# mbed-WiFi-BLE-Cloud-v1_0_0.net
KiCad netlist of a schematic drawn in EAGLE
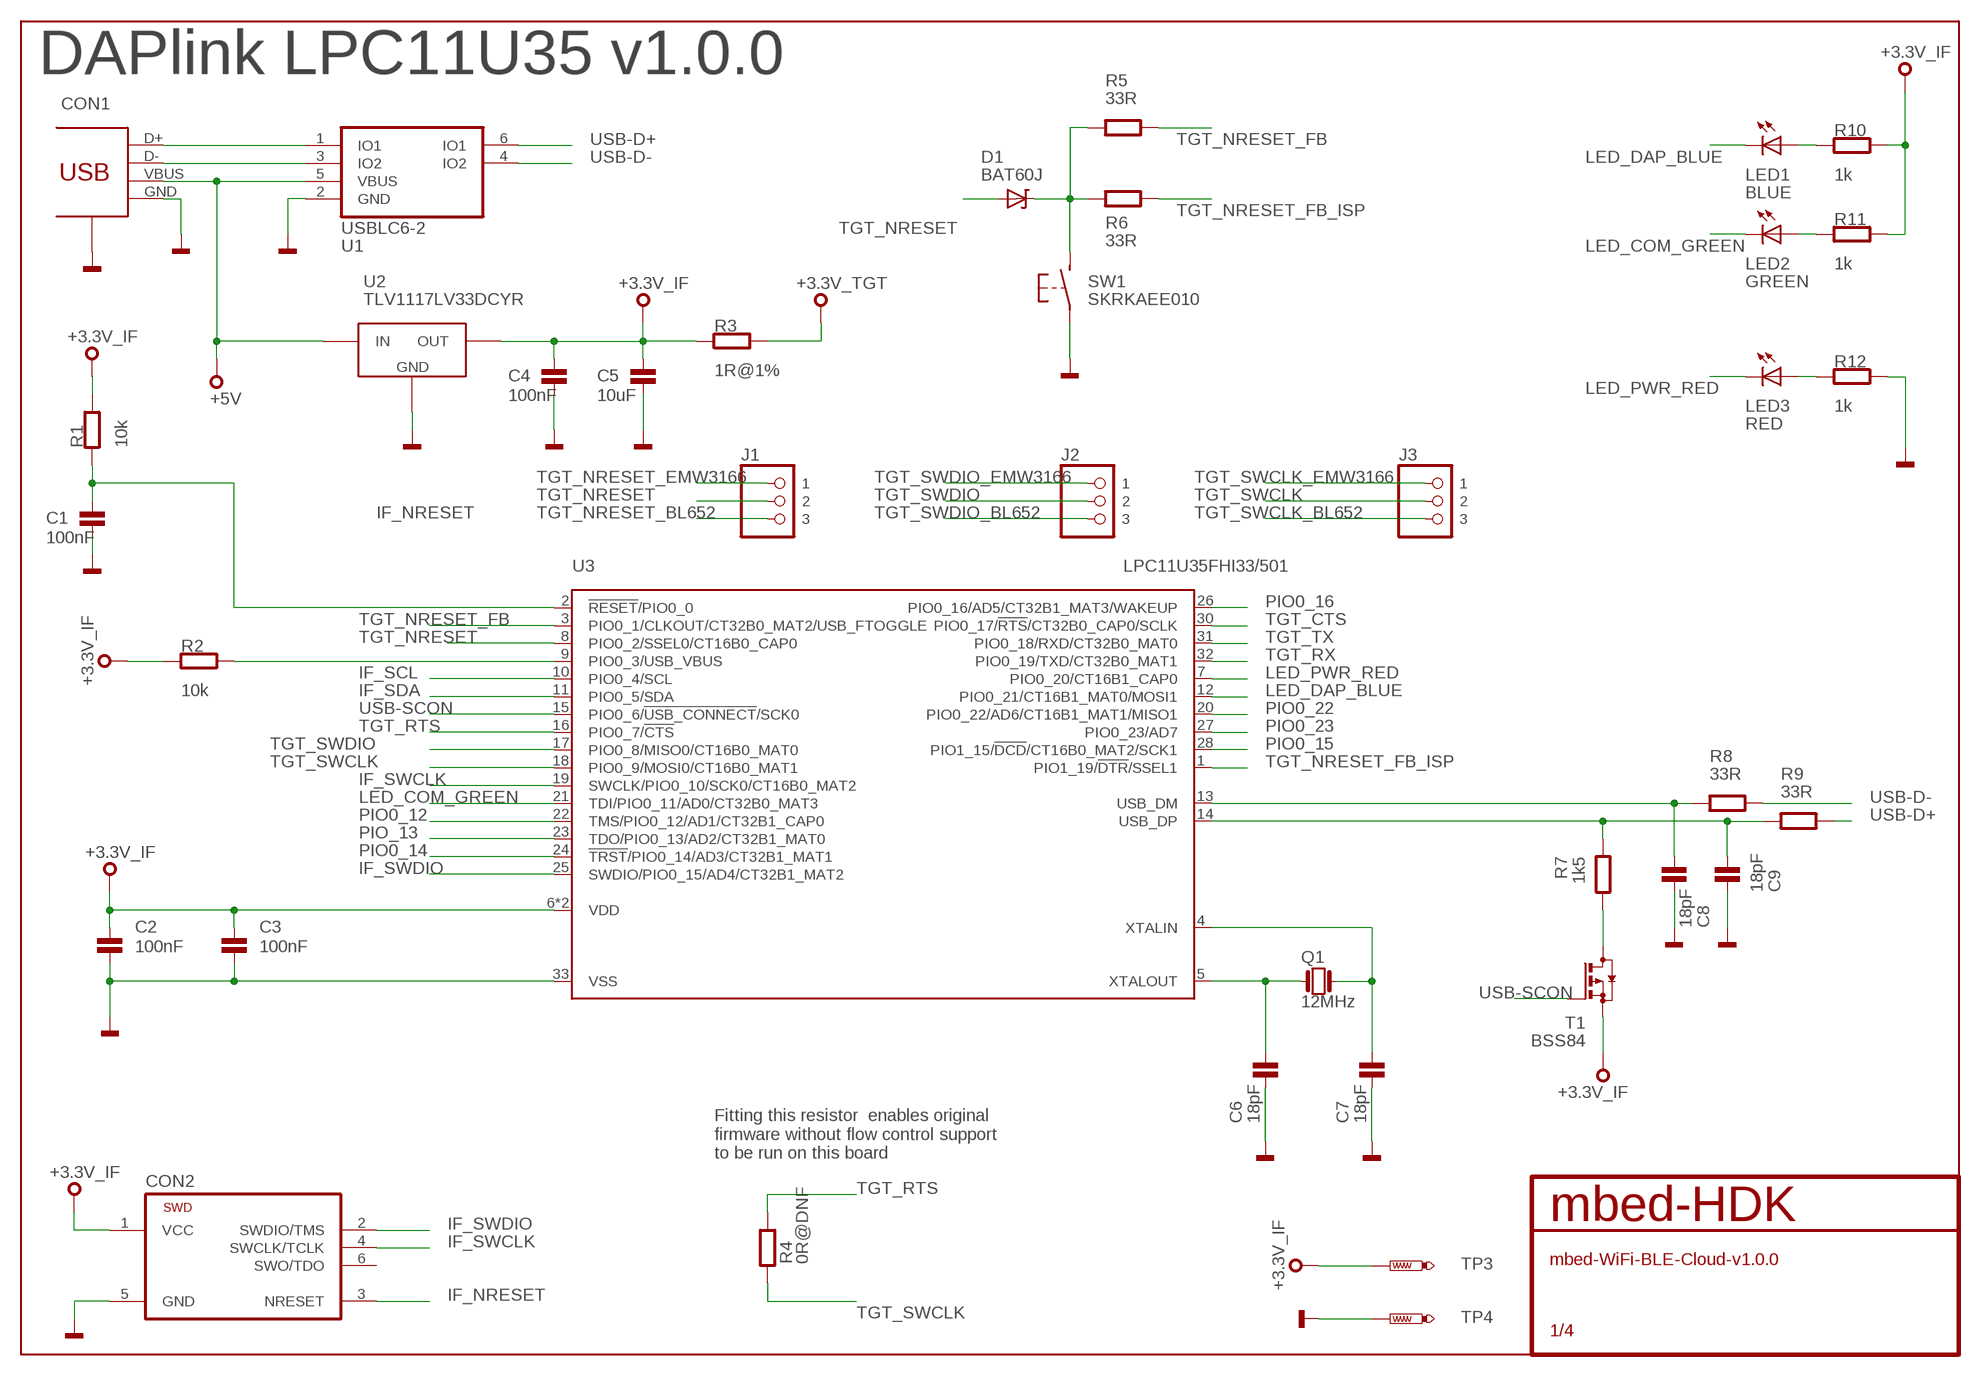
[diagram p0: schematic, sheet 1]
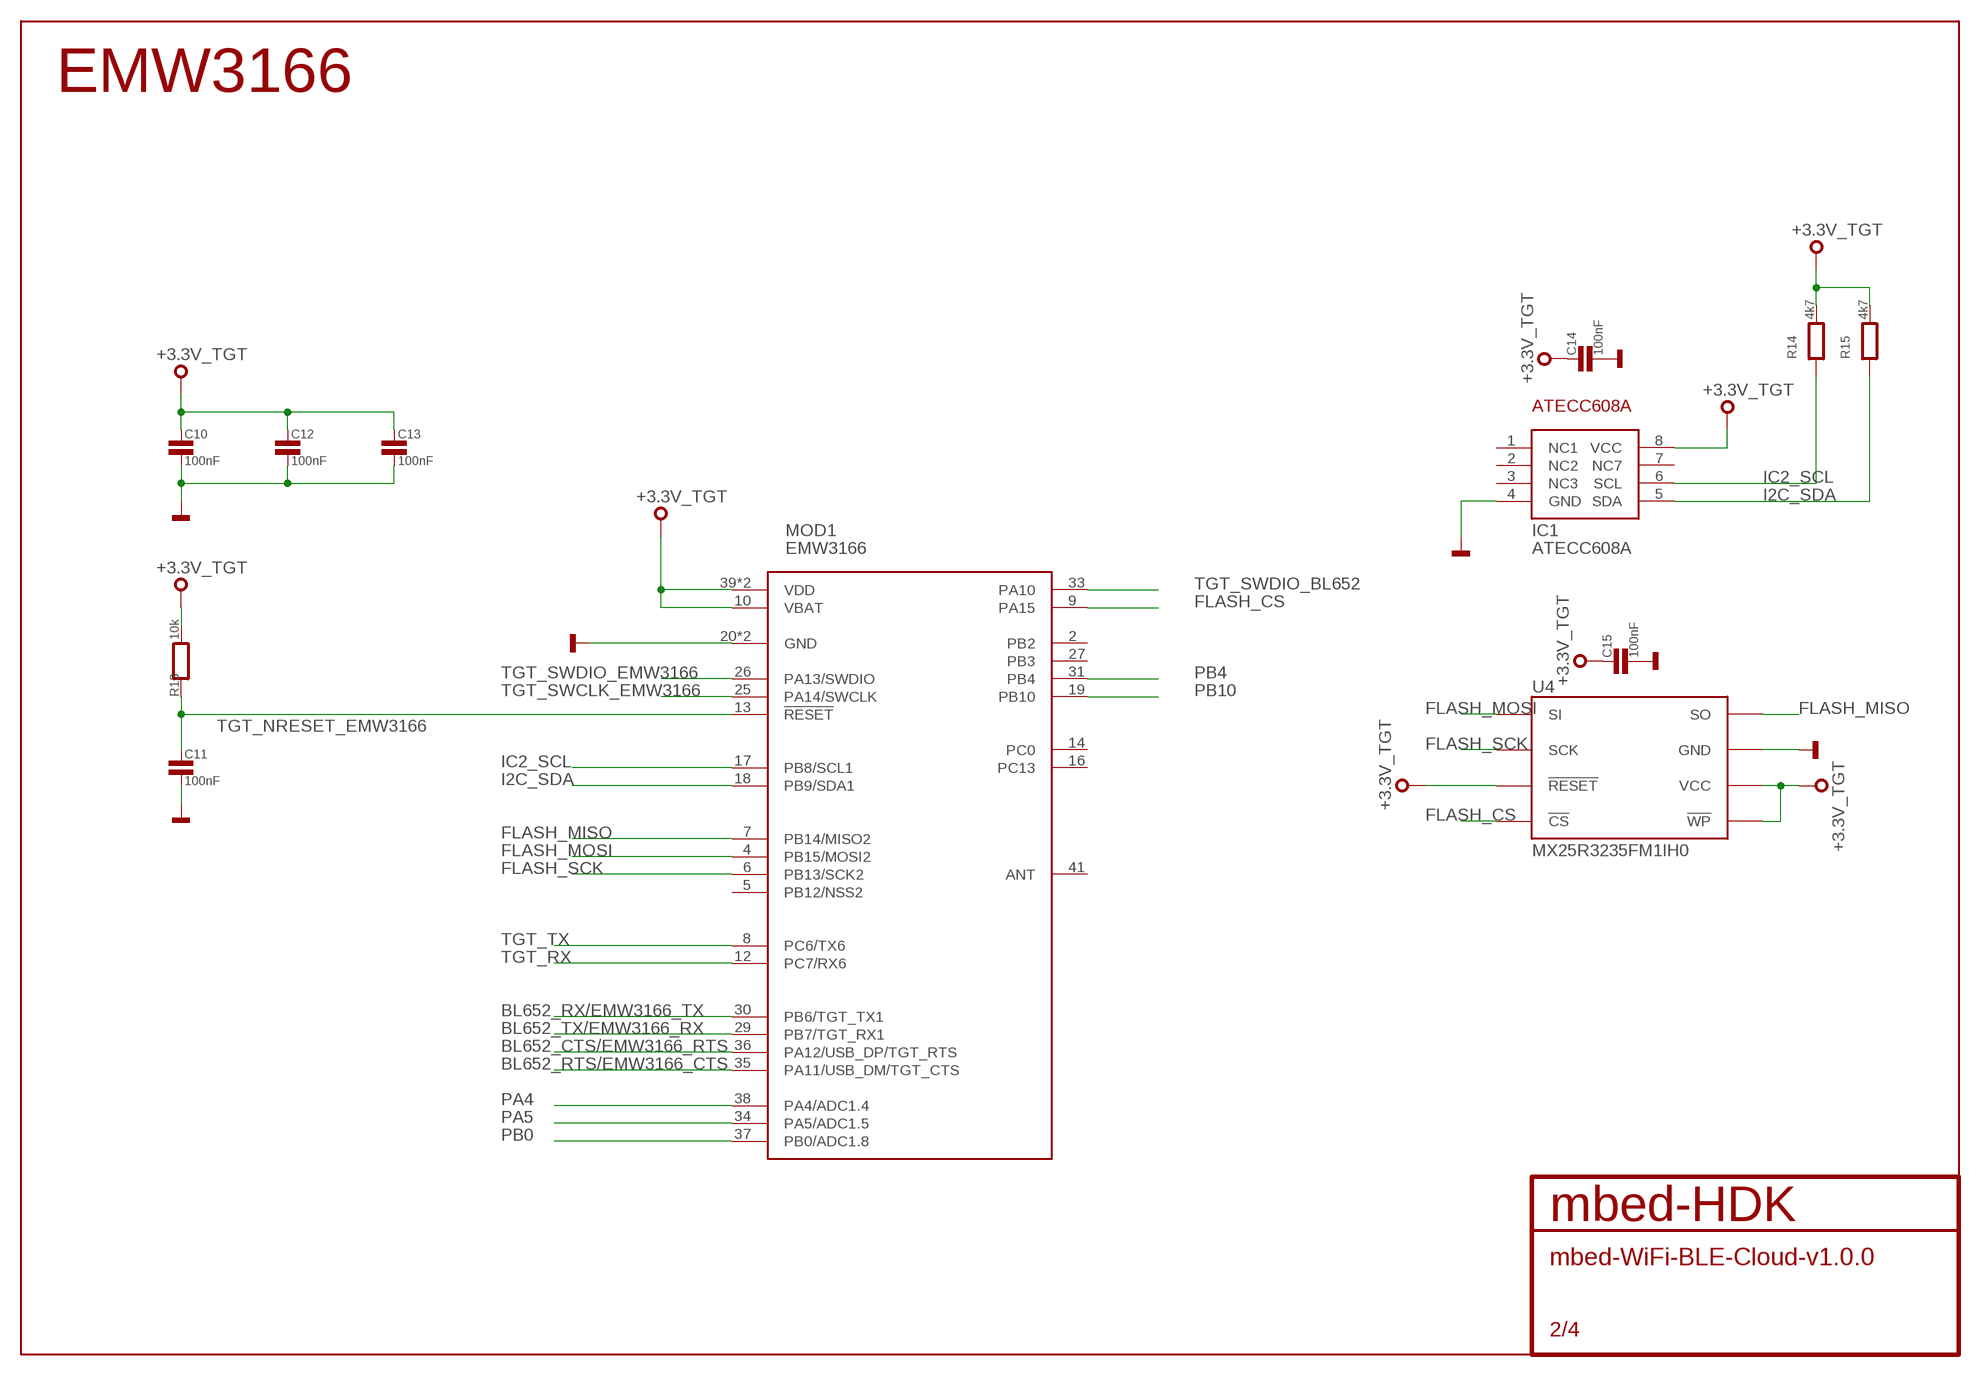
[diagram p1: schematic, sheet 2]
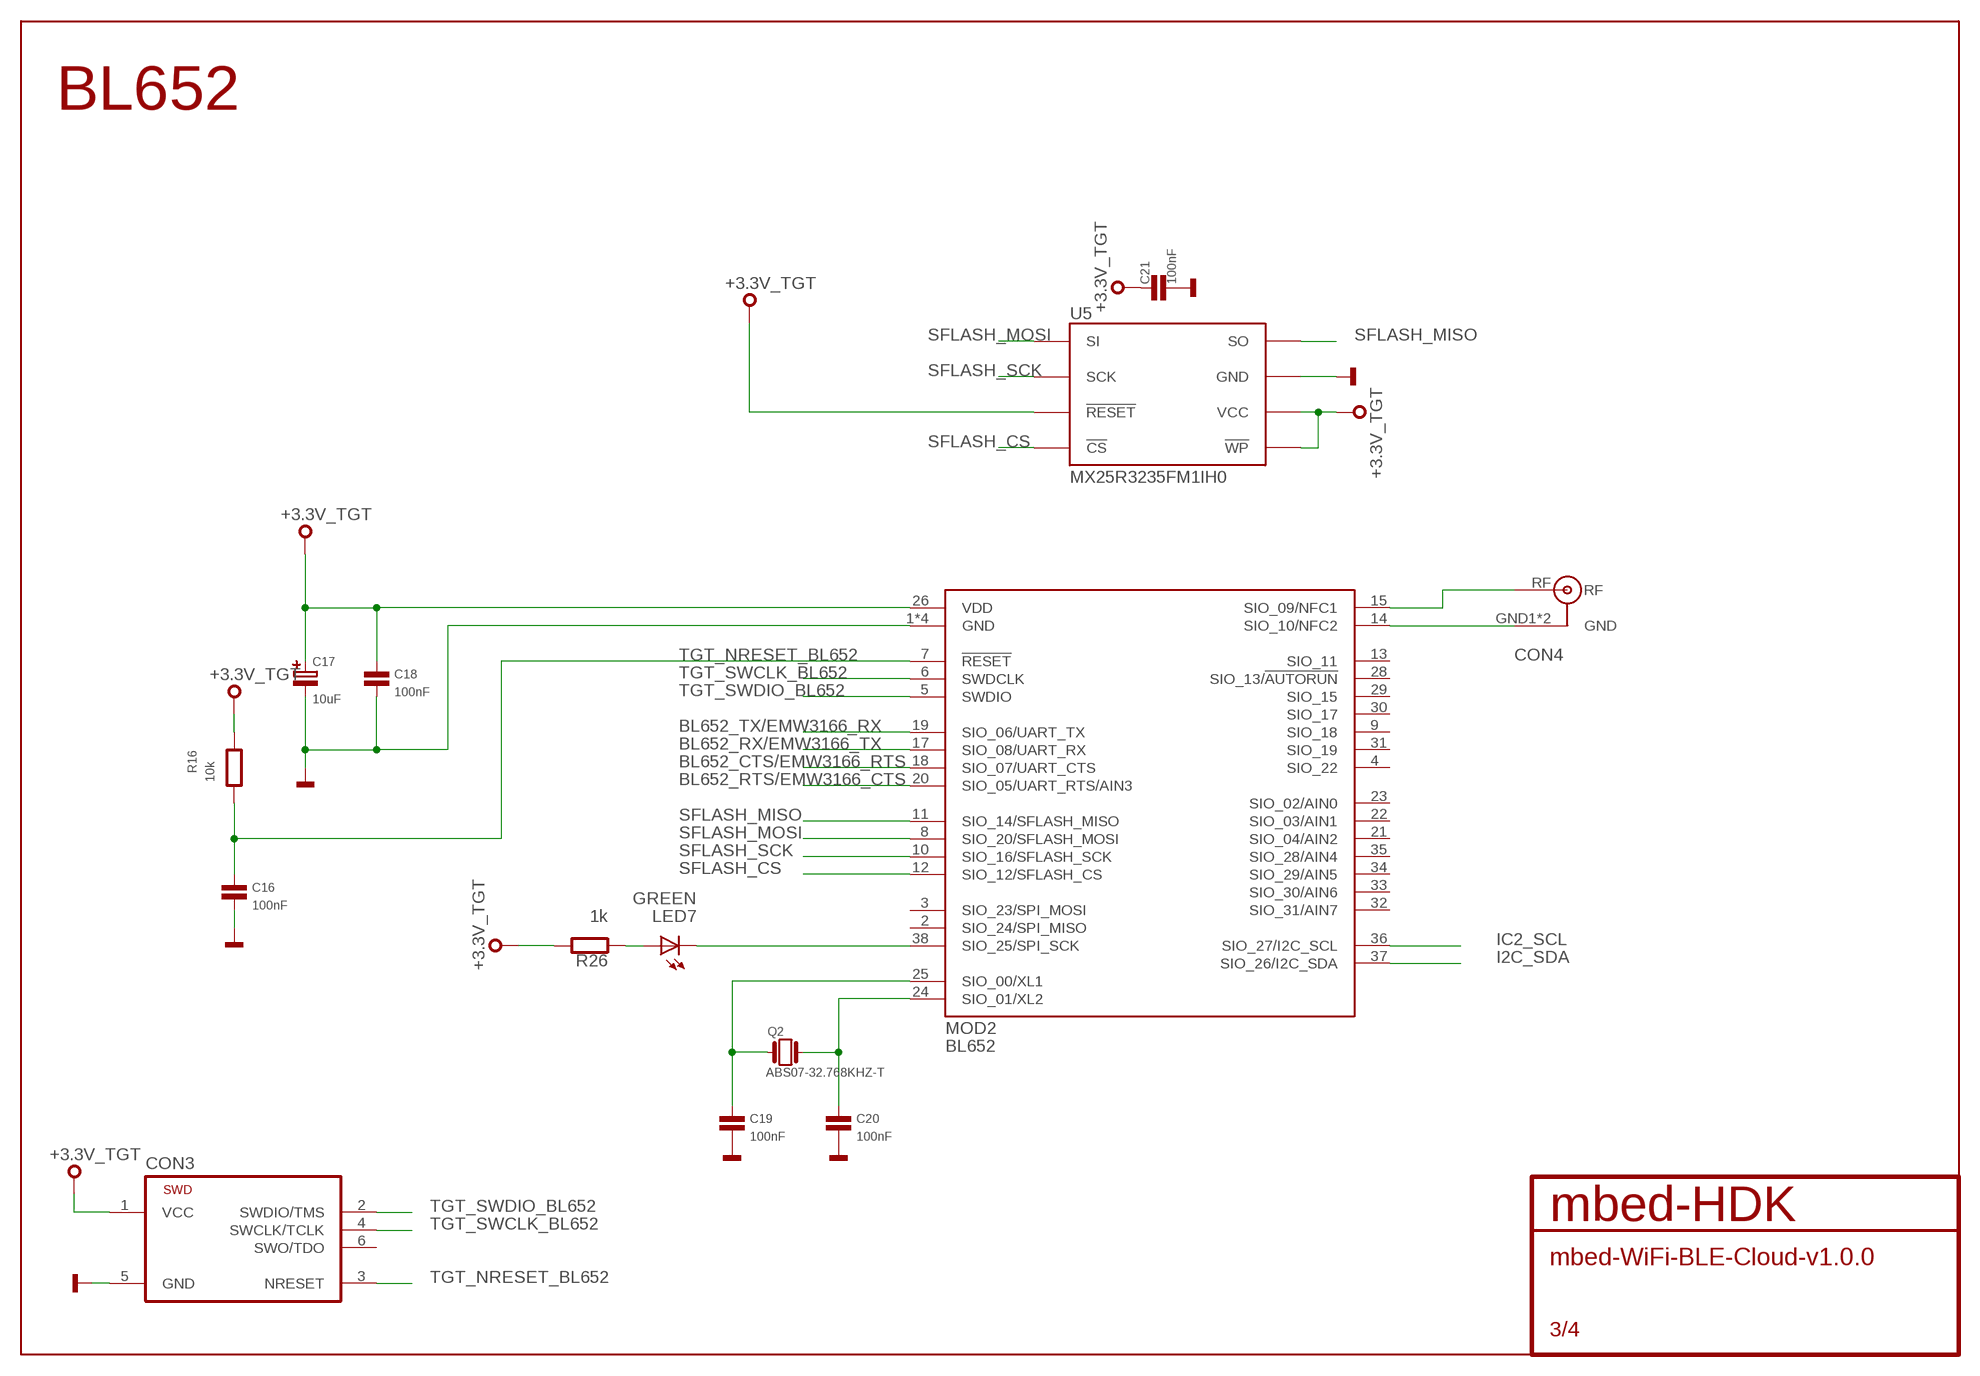
[diagram p2: schematic, sheet 3]
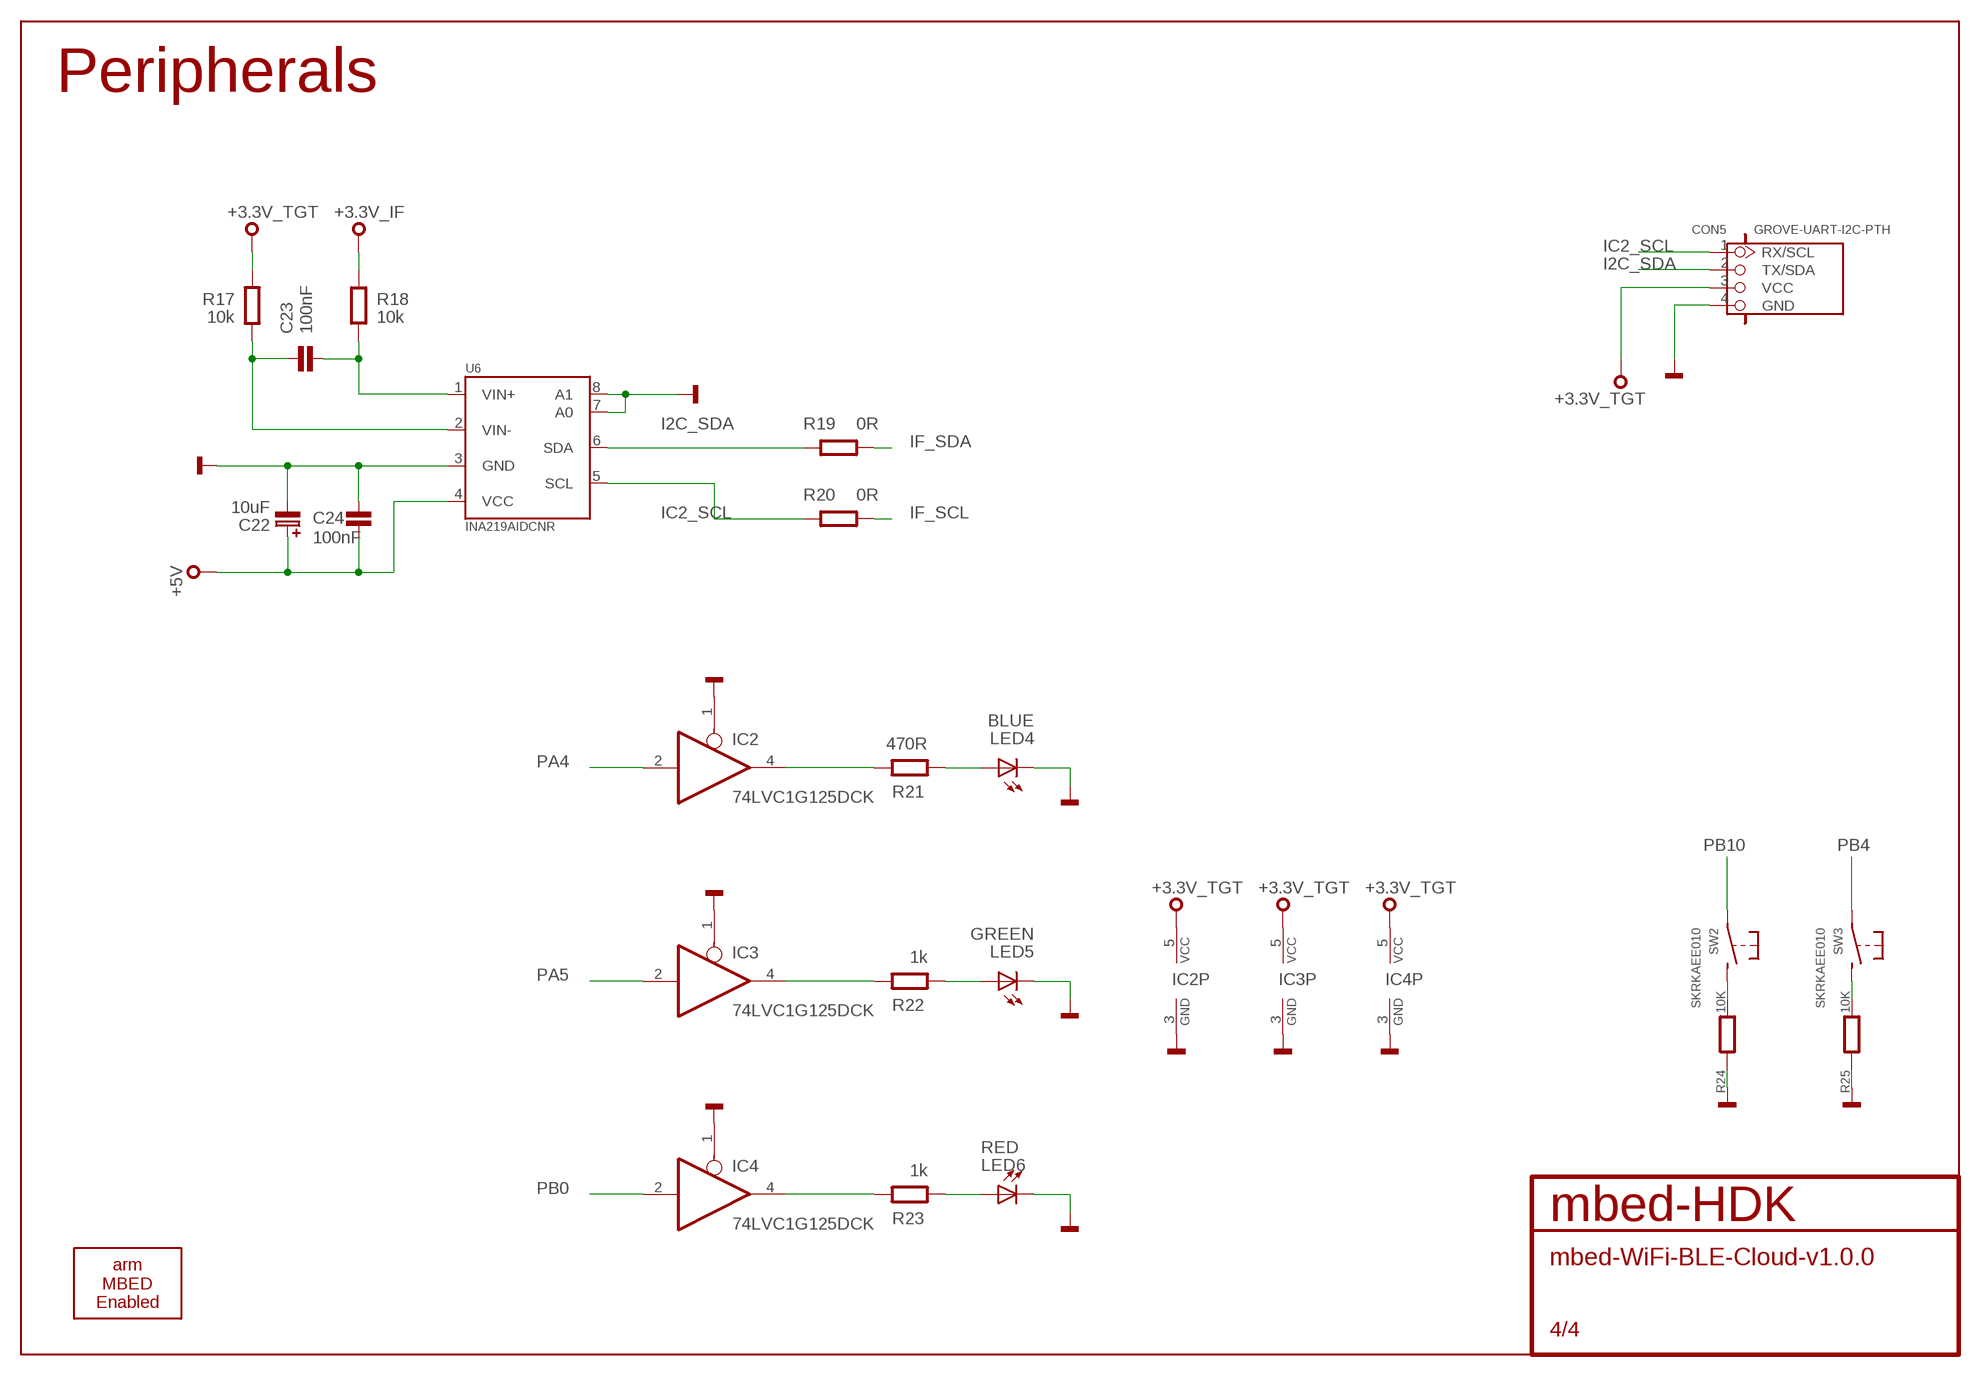
[diagram p3: schematic, sheet 4]

(export (version "E")
  (design (tool "Eeschema 10.0.6"))
  (components
    (comp (ref "C1")
      (value "100nF")
      (footprint "eagle-import:0603")
      (libsource (lib "eagle-import") (part "mbed-HDK-RLC_C0603"))
    )
    (comp (ref "C2")
      (value "100nF")
      (footprint "eagle-import:0603")
      (libsource (lib "eagle-import") (part "mbed-HDK-RLC_C0603"))
    )
    (comp (ref "C3")
      (value "100nF")
      (footprint "eagle-import:0603")
      (libsource (lib "eagle-import") (part "mbed-HDK-RLC_C0603"))
    )
    (comp (ref "C4")
      (value "100nF")
      (footprint "eagle-import:0603")
      (libsource (lib "eagle-import") (part "mbed-HDK-RLC_C0603"))
    )
    (comp (ref "C5")
      (value "10uF")
      (footprint "eagle-import:0603")
      (libsource (lib "eagle-import") (part "mbed-HDK-RLC_C0603"))
    )
    (comp (ref "C6")
      (value "18pF")
      (footprint "eagle-import:0603")
      (libsource (lib "eagle-import") (part "mbed-HDK-RLC_C0603"))
    )
    (comp (ref "C7")
      (value "18pF")
      (footprint "eagle-import:0603")
      (libsource (lib "eagle-import") (part "mbed-HDK-RLC_C0603"))
    )
    (comp (ref "C8")
      (value "18pF")
      (footprint "eagle-import:0603")
      (libsource (lib "eagle-import") (part "mbed-HDK-RLC_C0603"))
    )
    (comp (ref "C9")
      (value "18pF")
      (footprint "eagle-import:0603")
      (libsource (lib "eagle-import") (part "mbed-HDK-RLC_C0603"))
    )
    (comp (ref "CON1")
      (value "47346-0001")
      (footprint "eagle-import:USB-MICRO-B-H")
      (fields (field (name "MF") "MOLEX"))
      (libsource (lib "eagle-import") (part "47346-0001"))
    )
    (comp (ref "CON2")
      (value "TC2030-CTX-NL")
      (footprint "eagle-import:TC2030-CTX-NL")
      (libsource (lib "eagle-import") (part "TC2030-CTX-NL"))
    )
    (comp (ref "D1")
      (value "BAT60J")
      (footprint "eagle-import:SOD323")
      (fields (field (name "MF") "STMicroelectronics"))
      (libsource (lib "eagle-import") (part "BAT60J"))
    )
    (comp (ref "J1")
      (value "PINHD-1X3")
      (footprint "eagle-import:1X03")
      (libsource (lib "eagle-import") (part "PINHD-1X3"))
    )
    (comp (ref "J2")
      (value "PINHD-1X3")
      (footprint "eagle-import:1X03")
      (libsource (lib "eagle-import") (part "PINHD-1X3"))
    )
    (comp (ref "J3")
      (value "PINHD-1X3")
      (footprint "eagle-import:1X03")
      (libsource (lib "eagle-import") (part "PINHD-1X3"))
    )
    (comp (ref "LED1")
      (value "BLUE")
      (footprint "eagle-import:CHIPLED_0603")
      (libsource (lib "eagle-import") (part "mbed-HDK-Optical_LED0603"))
    )
    (comp (ref "LED2")
      (value "GREEN")
      (footprint "eagle-import:CHIPLED_0603")
      (libsource (lib "eagle-import") (part "mbed-HDK-Optical_LED0603"))
    )
    (comp (ref "LED3")
      (value "RED")
      (footprint "eagle-import:CHIPLED_0603")
      (libsource (lib "eagle-import") (part "mbed-HDK-Optical_LED0603"))
    )
    (comp (ref "Q1")
      (value "12MHz")
      (footprint "eagle-import:3.2X.2.5")
      (libsource (lib "eagle-import") (part "Q_3.2X2.5"))
    )
    (comp (ref "R1")
      (value "10k")
      (footprint "eagle-import:0603")
      (libsource (lib "eagle-import") (part "mbed-HDK-RLC_R0603"))
    )
    (comp (ref "R2")
      (value "10k")
      (footprint "eagle-import:0603")
      (libsource (lib "eagle-import") (part "mbed-HDK-RLC_R0603"))
    )
    (comp (ref "R3")
      (value "1R@1%")
      (footprint "eagle-import:0603")
      (libsource (lib "eagle-import") (part "mbed-HDK-RLC_R0603"))
    )
    (comp (ref "R4")
      (value "0R@DNF")
      (footprint "eagle-import:0603")
      (libsource (lib "eagle-import") (part "mbed-HDK-RLC_R0603"))
    )
    (comp (ref "R5")
      (value "33R")
      (footprint "eagle-import:0603")
      (libsource (lib "eagle-import") (part "mbed-HDK-RLC_R0603"))
    )
    (comp (ref "R6")
      (value "33R")
      (footprint "eagle-import:0603")
      (libsource (lib "eagle-import") (part "mbed-HDK-RLC_R0603"))
    )
    (comp (ref "R7")
      (value "1k5")
      (footprint "eagle-import:0603")
      (libsource (lib "eagle-import") (part "mbed-HDK-RLC_R0603"))
    )
    (comp (ref "R8")
      (value "33R")
      (footprint "eagle-import:0603")
      (libsource (lib "eagle-import") (part "mbed-HDK-RLC_R0603"))
    )
    (comp (ref "R9")
      (value "33R")
      (footprint "eagle-import:0603")
      (libsource (lib "eagle-import") (part "mbed-HDK-RLC_R0603"))
    )
    (comp (ref "R10")
      (value "1k")
      (footprint "eagle-import:0603")
      (libsource (lib "eagle-import") (part "mbed-HDK-RLC_R0603"))
    )
    (comp (ref "R11")
      (value "1k")
      (footprint "eagle-import:0603")
      (libsource (lib "eagle-import") (part "mbed-HDK-RLC_R0603"))
    )
    (comp (ref "R12")
      (value "1k")
      (footprint "eagle-import:0603")
      (libsource (lib "eagle-import") (part "mbed-HDK-RLC_R0603"))
    )
    (comp (ref "SW1")
      (value "SKRKAEE010")
      (footprint "eagle-import:SKRKAEE010")
      (fields (field (name "MF") "ALPS"))
      (libsource (lib "eagle-import") (part "SKRKAEE010"))
    )
    (comp (ref "T1")
      (value "BSS84")
      (footprint "eagle-import:SOT23-3")
      (fields (field (name "MF") "Fairchild Semiconductor"))
      (libsource (lib "eagle-import") (part "BSS84"))
    )
    (comp (ref "TP3")
      (value "PTR1PAD1-13")
      (footprint "eagle-import:P1-13")
      (libsource (lib "eagle-import") (part "PTR1PAD1-13"))
    )
    (comp (ref "TP4")
      (value "PTR1PAD1-13")
      (footprint "eagle-import:P1-13")
      (libsource (lib "eagle-import") (part "PTR1PAD1-13"))
    )
    (comp (ref "U1")
      (value "USBLC6-2SC6")
      (footprint "eagle-import:SOT23-6L")
      (libsource (lib "eagle-import") (part "USBLC6-2SC6"))
    )
    (comp (ref "U2")
      (value "TLV1117LV33DCYR")
      (footprint "eagle-import:SOT223")
      (fields (field (name "MF") "Texas Instruments"))
      (libsource (lib "eagle-import") (part "TLV1117LV33DCYR"))
    )
    (comp (ref "U3")
      (value "LPC11U35FHI33/501")
      (footprint "eagle-import:SOT617-3")
      (fields (field (name "MF") "NXP"))
      (libsource (lib "eagle-import") (part "LPC11U35FHI33/501"))
    )
    (comp (ref "C16")
      (value "100nF")
      (footprint "eagle-import:0603")
      (libsource (lib "eagle-import") (part "C0603"))
    )
    (comp (ref "C17")
      (value "10uF")
      (footprint "eagle-import:SMC_B")
      (fields (field (name "MF") "Kemet"))
      (libsource (lib "eagle-import") (part "CAPACITOR-POLARISEDB"))
    )
    (comp (ref "C18")
      (value "100nF")
      (footprint "eagle-import:0603")
      (libsource (lib "eagle-import") (part "C0603"))
    )
    (comp (ref "C19")
      (value "100nF")
      (footprint "eagle-import:0603")
      (libsource (lib "eagle-import") (part "C0603"))
    )
    (comp (ref "C20")
      (value "100nF")
      (footprint "eagle-import:0603")
      (libsource (lib "eagle-import") (part "C0603"))
    )
    (comp (ref "C21")
      (value "100nF")
      (footprint "eagle-import:0603")
      (libsource (lib "eagle-import") (part "CAPACITOR0603"))
    )
    (comp (ref "CON3")
      (value "TC2030-CTX-NL")
      (footprint "eagle-import:TC2030-CTX-NL")
      (libsource (lib "eagle-import") (part "TC2030-CTX-NL"))
    )
    (comp (ref "CON4")
      (value "U.FL")
      (footprint "eagle-import:U.FL-R-SMT-1")
      (fields (field (name "MF") "Hirose"))
      (libsource (lib "eagle-import") (part "U.FL"))
    )
    (comp (ref "LED7")
      (value "GREEN")
      (footprint "eagle-import:CHIPLED_0603")
      (libsource (lib "eagle-import") (part "mbed-HDK-Optical_LED0603"))
    )
    (comp (ref "MOD2")
      (value "BL652")
      (footprint "eagle-import:BL652")
      (libsource (lib "eagle-import") (part "BL652"))
    )
    (comp (ref "Q2")
      (value "ABS07-32.768KHZ-T")
      (footprint "eagle-import:FC135")
      (fields (field (name "MF") "Abracon"))
      (libsource (lib "eagle-import") (part "ABS07-32.768KHZ-T"))
    )
    (comp (ref "R16")
      (value "10k")
      (footprint "eagle-import:0603")
      (libsource (lib "eagle-import") (part "RESISTOR0603"))
    )
    (comp (ref "R26")
      (value "1k")
      (footprint "eagle-import:0603")
      (libsource (lib "eagle-import") (part "mbed-HDK-RLC_R0603"))
    )
    (comp (ref "U5")
      (value "MX25R3235FM1IH0")
      (footprint "eagle-import:SO8")
      (fields (field (name "MF") "Macronix"))
      (libsource (lib "eagle-import") (part "MX25R3235FM1IH0"))
    )
    (comp (ref "C10")
      (value "100nF")
      (footprint "eagle-import:0603")
      (libsource (lib "eagle-import") (part "CAPACITOR0603"))
    )
    (comp (ref "C11")
      (value "100nF")
      (footprint "eagle-import:0603")
      (libsource (lib "eagle-import") (part "CAPACITOR0603"))
    )
    (comp (ref "C12")
      (value "100nF")
      (footprint "eagle-import:0603")
      (libsource (lib "eagle-import") (part "CAPACITOR0603"))
    )
    (comp (ref "C13")
      (value "100nF")
      (footprint "eagle-import:0603")
      (libsource (lib "eagle-import") (part "CAPACITOR0603"))
    )
    (comp (ref "C14")
      (value "100nF")
      (footprint "eagle-import:0603")
      (libsource (lib "eagle-import") (part "CAPACITOR0603"))
    )
    (comp (ref "C15")
      (value "100nF")
      (footprint "eagle-import:0603")
      (libsource (lib "eagle-import") (part "CAPACITOR0603"))
    )
    (comp (ref "IC1")
      (value "ATECC608A")
      (footprint "eagle-import:SO8")
      (libsource (lib "eagle-import") (part "ATECC608A"))
    )
    (comp (ref "MOD1")
      (value "EMW3166")
      (footprint "eagle-import:EMW3166")
      (libsource (lib "eagle-import") (part "EMW3166"))
    )
    (comp (ref "R13")
      (value "10k")
      (footprint "eagle-import:0603")
      (libsource (lib "eagle-import") (part "RESISTOR0603"))
    )
    (comp (ref "R14")
      (value "4k7")
      (footprint "eagle-import:0603")
      (libsource (lib "eagle-import") (part "RESISTOR0603"))
    )
    (comp (ref "R15")
      (value "4k7")
      (footprint "eagle-import:0603")
      (libsource (lib "eagle-import") (part "RESISTOR0603"))
    )
    (comp (ref "U4")
      (value "MX25R3235FM1IH0")
      (footprint "eagle-import:SO8")
      (fields (field (name "MF") "Macronix"))
      (libsource (lib "eagle-import") (part "MX25R3235FM1IH0"))
    )
    (comp (ref "C22")
      (value "10uF")
      (footprint "eagle-import:CASE-B")
      (libsource (lib "eagle-import") (part "C-POL_B"))
    )
    (comp (ref "C23")
      (value "100nF")
      (footprint "eagle-import:0603")
      (libsource (lib "eagle-import") (part "C0603"))
    )
    (comp (ref "C24")
      (value "100nF")
      (footprint "eagle-import:0603")
      (libsource (lib "eagle-import") (part "C0603"))
    )
    (comp (ref "CON5")
      (value "GROVE-UART-I2C-PTH")
      (footprint "eagle-import:HW4-2.0")
      (libsource (lib "eagle-import") (part "GROVE-UART-I2C-PTH"))
    )
    (comp (ref "IC2")
      (value "74LVC1G125DCK")
      (footprint "eagle-import:SC70-5")
      (libsource (lib "eagle-import") (part "741G125DCKLVC"))
    )
    (comp (ref "IC3")
      (value "74LVC1G125DCK")
      (footprint "eagle-import:SC70-5")
      (libsource (lib "eagle-import") (part "741G125DCKLVC"))
    )
    (comp (ref "IC4")
      (value "74LVC1G125DCK")
      (footprint "eagle-import:SC70-5")
      (libsource (lib "eagle-import") (part "741G125DCKLVC"))
    )
    (comp (ref "LED4")
      (value "BLUE")
      (footprint "eagle-import:CHIPLED_0603")
      (libsource (lib "eagle-import") (part "LED0603"))
    )
    (comp (ref "LED5")
      (value "GREEN")
      (footprint "eagle-import:CHIPLED_0603")
      (libsource (lib "eagle-import") (part "LED0603"))
    )
    (comp (ref "LED6")
      (value "RED")
      (footprint "eagle-import:CHIPLED_0603")
      (libsource (lib "eagle-import") (part "LED0603"))
    )
    (comp (ref "R17")
      (value "10k")
      (footprint "eagle-import:0603@1")
      (libsource (lib "eagle-import") (part "R0603"))
    )
    (comp (ref "R18")
      (value "10k")
      (footprint "eagle-import:0603@1")
      (libsource (lib "eagle-import") (part "R0603"))
    )
    (comp (ref "R19")
      (value "0R")
      (footprint "eagle-import:0603@1")
      (libsource (lib "eagle-import") (part "R0603"))
    )
    (comp (ref "R20")
      (value "0R")
      (footprint "eagle-import:0603@1")
      (libsource (lib "eagle-import") (part "R0603"))
    )
    (comp (ref "R21")
      (value "470R")
      (footprint "eagle-import:0603@1")
      (libsource (lib "eagle-import") (part "R0603"))
    )
    (comp (ref "R22")
      (value "1k")
      (footprint "eagle-import:0603@1")
      (libsource (lib "eagle-import") (part "R0603"))
    )
    (comp (ref "R23")
      (value "1k")
      (footprint "eagle-import:0603@1")
      (libsource (lib "eagle-import") (part "R0603"))
    )
    (comp (ref "R24")
      (value "10K")
      (footprint "eagle-import:0603")
      (libsource (lib "eagle-import") (part "RESISTOR0603"))
    )
    (comp (ref "R25")
      (value "10K")
      (footprint "eagle-import:0603")
      (libsource (lib "eagle-import") (part "RESISTOR0603"))
    )
    (comp (ref "SS1")
      (value "ARM-MBED-ENABLED-12MM")
      (footprint "eagle-import:ARM-MBED-ENABLED-12MM")
      (libsource (lib "eagle-import") (part "ARM-MBED-ENABLED-12MM"))
    )
    (comp (ref "SW2")
      (value "SKRKAEE010")
      (footprint "eagle-import:SKRKAEE010")
      (fields (field (name "MF") "ALPS"))
      (libsource (lib "eagle-import") (part "SKRKAEE010"))
    )
    (comp (ref "SW3")
      (value "SKRKAEE010")
      (footprint "eagle-import:SKRKAEE010")
      (fields (field (name "MF") "ALPS"))
      (libsource (lib "eagle-import") (part "SKRKAEE010"))
    )
    (comp (ref "U6")
      (value "INA219AIDCNR")
      (footprint "eagle-import:SOT23-8")
      (fields (field (name "MF") "Texas Instruments"))
      (libsource (lib "eagle-import") (part "INA219AIDCNR"))
    )
  )
  (nets
    (net (code "1") (name "+3.3V_IF") (class "Default")
      (node (ref "C2") (pin "1") (pinfunction "P$1_1") (pintype "passive"))
      (node (ref "C3") (pin "1") (pinfunction "P$1_1") (pintype "passive"))
      (node (ref "C4") (pin "1") (pinfunction "P$1_1") (pintype "passive"))
      (node (ref "C5") (pin "1") (pinfunction "P$1_1") (pintype "passive"))
      (node (ref "CON2") (pin "1") (pinfunction "VCC_1") (pintype "passive"))
      (node (ref "R1") (pin "2") (pinfunction "P$2_2") (pintype "passive"))
      (node (ref "R10") (pin "2") (pinfunction "P$2_2") (pintype "passive"))
      (node (ref "R11") (pin "2") (pinfunction "P$2_2") (pintype "passive"))
      (node (ref "R18") (pin "2") (pinfunction "P$2_2") (pintype "passive"))
      (node (ref "R2") (pin "1") (pinfunction "P$1_1") (pintype "passive"))
      (node (ref "R3") (pin "1") (pinfunction "P$1_1") (pintype "passive"))
      (node (ref "T1") (pin "2") (pinfunction "S_2") (pintype "passive"))
      (node (ref "TP3") (pin "TP") (pinfunction "TP_TP") (pintype "input"))
      (node (ref "U2") (pin "2") (pinfunction "OUT_2") (pintype "bidirectional"))
      (node (ref "U2") (pin "4") (pinfunction "OUT_4") (pintype "bidirectional"))
      (node (ref "U3") (pin "29") (pinfunction "VDD_29") (pintype "passive"))
      (node (ref "U3") (pin "6") (pinfunction "VDD_6") (pintype "passive"))
    )
    (net (code "2") (name "+3.3V_TGT") (class "Default")
      (node (ref "C10") (pin "1") (pinfunction "P$1_1") (pintype "passive"))
      (node (ref "C12") (pin "1") (pinfunction "P$1_1") (pintype "passive"))
      (node (ref "C13") (pin "1") (pinfunction "P$1_1") (pintype "passive"))
      (node (ref "C14") (pin "1") (pinfunction "P$1_1") (pintype "passive"))
      (node (ref "C15") (pin "1") (pinfunction "P$1_1") (pintype "passive"))
      (node (ref "C17") (pin "+") (pinfunction "+_+") (pintype "passive"))
      (node (ref "C18") (pin "1") (pinfunction "P$1_1") (pintype "passive"))
      (node (ref "C21") (pin "1") (pinfunction "P$1_1") (pintype "passive"))
      (node (ref "CON3") (pin "1") (pinfunction "VCC_1") (pintype "passive"))
      (node (ref "CON5") (pin "3") (pinfunction "VCC_3") (pintype "bidirectional"))
      (node (ref "IC1") (pin "8") (pinfunction "VCC_8") (pintype "bidirectional"))
      (node (ref "IC2") (pin "5") (pinfunction "VCC_5") (pintype "power_in"))
      (node (ref "IC3") (pin "5") (pinfunction "VCC_5") (pintype "power_in"))
      (node (ref "IC4") (pin "5") (pinfunction "VCC_5") (pintype "power_in"))
      (node (ref "MOD1") (pin "10") (pinfunction "VBAT_10") (pintype "bidirectional"))
      (node (ref "MOD1") (pin "39") (pinfunction "VDD_39") (pintype "bidirectional"))
      (node (ref "MOD1") (pin "40") (pinfunction "VDD_40") (pintype "bidirectional"))
      (node (ref "MOD2") (pin "26") (pinfunction "VDD_26") (pintype "bidirectional"))
      (node (ref "R13") (pin "2") (pinfunction "P$2_2") (pintype "passive"))
      (node (ref "R14") (pin "2") (pinfunction "P$2_2") (pintype "passive"))
      (node (ref "R15") (pin "2") (pinfunction "P$2_2") (pintype "passive"))
      (node (ref "R16") (pin "2") (pinfunction "P$2_2") (pintype "passive"))
      (node (ref "R17") (pin "2") (pinfunction "P$2_2") (pintype "passive"))
      (node (ref "R26") (pin "2") (pinfunction "P$2_2") (pintype "passive"))
      (node (ref "R3") (pin "2") (pinfunction "P$2_2") (pintype "passive"))
      (node (ref "U4") (pin "3") (pinfunction "~{WP}_3") (pintype "bidirectional"))
      (node (ref "U4") (pin "7") (pinfunction "~{RESET}_7") (pintype "bidirectional"))
      (node (ref "U4") (pin "8") (pinfunction "VCC_8") (pintype "bidirectional"))
      (node (ref "U5") (pin "3") (pinfunction "~{WP}_3") (pintype "bidirectional"))
      (node (ref "U5") (pin "7") (pinfunction "~{RESET}_7") (pintype "bidirectional"))
      (node (ref "U5") (pin "8") (pinfunction "VCC_8") (pintype "bidirectional"))
    )
    (net (code "3") (name "+5V") (class "Default")
      (node (ref "C22") (pin "1") (pinfunction "1_1") (pintype "passive"))
      (node (ref "C24") (pin "2") (pinfunction "P$2_2") (pintype "passive"))
      (node (ref "CON1") (pin "VBUS") (pinfunction "VBUS_VBUS") (pintype "bidirectional"))
      (node (ref "U1") (pin "5") (pinfunction "VBUS_5") (pintype "bidirectional"))
      (node (ref "U2") (pin "3") (pinfunction "IN_3") (pintype "bidirectional"))
      (node (ref "U6") (pin "4") (pinfunction "VCC_4") (pintype "power_in"))
    )
    (net (code "4") (name "BL652_CTS{slash}EMW3166_RTS") (class "Default")
      (node (ref "MOD1") (pin "36") (pinfunction "PA12/USB_DP/TGT_RTS_36") (pintype "bidirectional"))
      (node (ref "MOD2") (pin "18") (pinfunction "SIO_07/UART_CTS_18") (pintype "bidirectional"))
    )
    (net (code "5") (name "BL652_RTS{slash}EMW3166_CTS") (class "Default")
      (node (ref "MOD1") (pin "35") (pinfunction "PA11/USB_DM/TGT_CTS_35") (pintype "bidirectional"))
      (node (ref "MOD2") (pin "20") (pinfunction "SIO_05/UART_RTS/AIN3_20") (pintype "bidirectional"))
    )
    (net (code "6") (name "BL652_RX{slash}EMW3166_TX") (class "Default")
      (node (ref "MOD1") (pin "30") (pinfunction "PB6/TGT_TX1_30") (pintype "bidirectional"))
      (node (ref "MOD2") (pin "17") (pinfunction "SIO_08/UART_RX_17") (pintype "bidirectional"))
    )
    (net (code "7") (name "BL652_TX{slash}EMW3166_RX") (class "Default")
      (node (ref "MOD1") (pin "29") (pinfunction "PB7/TGT_RX1_29") (pintype "bidirectional"))
      (node (ref "MOD2") (pin "19") (pinfunction "SIO_06/UART_TX_19") (pintype "bidirectional"))
    )
    (net (code "8") (name "FLASH_CS") (class "Default")
      (node (ref "MOD1") (pin "9") (pinfunction "PA15_9") (pintype "bidirectional"))
      (node (ref "U4") (pin "1") (pinfunction "~{CS}_1") (pintype "bidirectional"))
    )
    (net (code "9") (name "FLASH_MISO") (class "Default")
      (node (ref "MOD1") (pin "7") (pinfunction "PB14/MISO2_7") (pintype "bidirectional"))
      (node (ref "U4") (pin "2") (pinfunction "SO_2") (pintype "bidirectional"))
    )
    (net (code "10") (name "FLASH_MOSI") (class "Default")
      (node (ref "MOD1") (pin "4") (pinfunction "PB15/MOSI2_4") (pintype "bidirectional"))
      (node (ref "U4") (pin "5") (pinfunction "SI_5") (pintype "bidirectional"))
    )
    (net (code "11") (name "FLASH_SCK") (class "Default")
      (node (ref "MOD1") (pin "6") (pinfunction "PB13/SCK2_6") (pintype "bidirectional"))
      (node (ref "U4") (pin "6") (pinfunction "SCK_6") (pintype "bidirectional"))
    )
    (net (code "12") (name "GND") (class "Default")
      (node (ref "C1") (pin "2") (pinfunction "P$2_2") (pintype "passive"))
      (node (ref "C10") (pin "2") (pinfunction "P$2_2") (pintype "passive"))
      (node (ref "C11") (pin "2") (pinfunction "P$2_2") (pintype "passive"))
      (node (ref "C12") (pin "2") (pinfunction "P$2_2") (pintype "passive"))
      (node (ref "C13") (pin "2") (pinfunction "P$2_2") (pintype "passive"))
      (node (ref "C14") (pin "2") (pinfunction "P$2_2") (pintype "passive"))
      (node (ref "C15") (pin "2") (pinfunction "P$2_2") (pintype "passive"))
      (node (ref "C16") (pin "2") (pinfunction "P$2_2") (pintype "passive"))
      (node (ref "C17") (pin "-") (pinfunction "-_-") (pintype "passive"))
      (node (ref "C18") (pin "2") (pinfunction "P$2_2") (pintype "passive"))
      (node (ref "C19") (pin "2") (pinfunction "P$2_2") (pintype "passive"))
      (node (ref "C2") (pin "2") (pinfunction "P$2_2") (pintype "passive"))
      (node (ref "C20") (pin "2") (pinfunction "P$2_2") (pintype "passive"))
      (node (ref "C21") (pin "2") (pinfunction "P$2_2") (pintype "passive"))
      (node (ref "C22") (pin "2") (pinfunction "2_2") (pintype "passive"))
      (node (ref "C24") (pin "1") (pinfunction "P$1_1") (pintype "passive"))
      (node (ref "C3") (pin "2") (pinfunction "P$2_2") (pintype "passive"))
      (node (ref "C4") (pin "2") (pinfunction "P$2_2") (pintype "passive"))
      (node (ref "C5") (pin "2") (pinfunction "P$2_2") (pintype "passive"))
      (node (ref "C6") (pin "2") (pinfunction "P$2_2") (pintype "passive"))
      (node (ref "C7") (pin "2") (pinfunction "P$2_2") (pintype "passive"))
      (node (ref "C8") (pin "2") (pinfunction "P$2_2") (pintype "passive"))
      (node (ref "C9") (pin "2") (pinfunction "P$2_2") (pintype "passive"))
      (node (ref "CON1") (pin "GND") (pinfunction "GND_GND") (pintype "bidirectional"))
      (node (ref "CON1") (pin "GND1") (pinfunction "SHEILD_GND1") (pintype "bidirectional"))
      (node (ref "CON1") (pin "GND2") (pinfunction "SHEILD_GND2") (pintype "bidirectional"))
      (node (ref "CON1") (pin "GND3") (pinfunction "SHEILD_GND3") (pintype "bidirectional"))
      (node (ref "CON1") (pin "GND4") (pinfunction "SHEILD_GND4") (pintype "bidirectional"))
      (node (ref "CON2") (pin "5") (pinfunction "GND_5") (pintype "passive"))
      (node (ref "CON3") (pin "5") (pinfunction "GND_5") (pintype "passive"))
      (node (ref "CON5") (pin "4") (pinfunction "GND_4") (pintype "bidirectional"))
      (node (ref "IC1") (pin "4") (pinfunction "GND_4") (pintype "bidirectional"))
      (node (ref "IC2") (pin "1") (pinfunction "OE_1") (pintype "input"))
      (node (ref "IC2") (pin "3") (pinfunction "GND_3") (pintype "power_in"))
      (node (ref "IC3") (pin "1") (pinfunction "OE_1") (pintype "input"))
      (node (ref "IC3") (pin "3") (pinfunction "GND_3") (pintype "power_in"))
      (node (ref "IC4") (pin "1") (pinfunction "OE_1") (pintype "input"))
      (node (ref "IC4") (pin "3") (pinfunction "GND_3") (pintype "power_in"))
      (node (ref "LED4") (pin "C") (pinfunction "C_C") (pintype "passive"))
      (node (ref "LED5") (pin "C") (pinfunction "C_C") (pintype "passive"))
      (node (ref "LED6") (pin "C") (pinfunction "C_C") (pintype "passive"))
      (node (ref "MOD1") (pin "20") (pinfunction "GND_20") (pintype "bidirectional"))
      (node (ref "MOD1") (pin "21") (pinfunction "GND_21") (pintype "bidirectional"))
      (node (ref "MOD2") (pin "1") (pinfunction "GND_1") (pintype "bidirectional"))
      (node (ref "MOD2") (pin "16") (pinfunction "GND_16") (pintype "bidirectional"))
      (node (ref "MOD2") (pin "27") (pinfunction "GND_27") (pintype "bidirectional"))
      (node (ref "MOD2") (pin "39") (pinfunction "GND_39") (pintype "bidirectional"))
      (node (ref "R12") (pin "2") (pinfunction "P$2_2") (pintype "passive"))
      (node (ref "R24") (pin "1") (pinfunction "P$1_1") (pintype "passive"))
      (node (ref "R25") (pin "1") (pinfunction "P$1_1") (pintype "passive"))
      (node (ref "SW1") (pin "P$1") (pinfunction "P_P$1") (pintype "passive"))
      (node (ref "TP4") (pin "TP") (pinfunction "TP_TP") (pintype "input"))
      (node (ref "U1") (pin "2") (pinfunction "GND_2") (pintype "bidirectional"))
      (node (ref "U2") (pin "1") (pinfunction "GND_1") (pintype "bidirectional"))
      (node (ref "U3") (pin "33") (pinfunction "VSS_33") (pintype "passive"))
      (node (ref "U4") (pin "4") (pinfunction "GND_4") (pintype "bidirectional"))
      (node (ref "U5") (pin "4") (pinfunction "GND_4") (pintype "bidirectional"))
      (node (ref "U6") (pin "3") (pinfunction "GND_3") (pintype "power_in"))
      (node (ref "U6") (pin "7") (pinfunction "A0_7") (pintype "input"))
      (node (ref "U6") (pin "8") (pinfunction "A1_8") (pintype "input"))
    )
    (net (code "13") (name "I2C_SDA") (class "Default")
      (node (ref "CON5") (pin "2") (pinfunction "TX/SDA_2") (pintype "bidirectional"))
      (node (ref "IC1") (pin "5") (pinfunction "SDA_5") (pintype "bidirectional"))
      (node (ref "MOD1") (pin "18") (pinfunction "PB9/SDA1_18") (pintype "bidirectional"))
      (node (ref "MOD2") (pin "37") (pinfunction "SIO_26/I2C_SDA_37") (pintype "bidirectional"))
      (node (ref "R15") (pin "1") (pinfunction "P$1_1") (pintype "passive"))
      (node (ref "R19") (pin "2") (pinfunction "P$2_2") (pintype "passive"))
      (node (ref "U6") (pin "6") (pinfunction "SDA_6") (pintype "bidirectional"))
    )
    (net (code "14") (name "IC2_SCL") (class "Default")
      (node (ref "CON5") (pin "1") (pinfunction "RX/SCL_1") (pintype "bidirectional"))
      (node (ref "IC1") (pin "6") (pinfunction "SCL_6") (pintype "bidirectional"))
      (node (ref "MOD1") (pin "17") (pinfunction "PB8/SCL1_17") (pintype "bidirectional"))
      (node (ref "MOD2") (pin "36") (pinfunction "SIO_27/I2C_SCL_36") (pintype "bidirectional"))
      (node (ref "R14") (pin "1") (pinfunction "P$1_1") (pintype "passive"))
      (node (ref "R20") (pin "2") (pinfunction "P$2_2") (pintype "passive"))
      (node (ref "U6") (pin "5") (pinfunction "SCL_5") (pintype "bidirectional"))
    )
    (net (code "15") (name "IF_NRESET") (class "Default")
      (node (ref "C1") (pin "1") (pinfunction "P$1_1") (pintype "passive"))
      (node (ref "CON2") (pin "3") (pinfunction "NRESET_3") (pintype "passive"))
      (node (ref "R1") (pin "1") (pinfunction "P$1_1") (pintype "passive"))
      (node (ref "U3") (pin "2") (pinfunction "~{RESET}/PIO0_0_2") (pintype "bidirectional"))
    )
    (net (code "16") (name "IF_SCL") (class "Default")
      (node (ref "R20") (pin "1") (pinfunction "P$1_1") (pintype "passive"))
      (node (ref "U3") (pin "10") (pinfunction "PIO0_4/SCL_10") (pintype "bidirectional"))
    )
    (net (code "17") (name "IF_SDA") (class "Default")
      (node (ref "R19") (pin "1") (pinfunction "P$1_1") (pintype "passive"))
      (node (ref "U3") (pin "11") (pinfunction "PIO0_5/SDA_11") (pintype "bidirectional"))
    )
    (net (code "18") (name "IF_SWCLK") (class "Default")
      (node (ref "CON2") (pin "4") (pinfunction "SWCLK/TCLK_4") (pintype "passive"))
      (node (ref "U3") (pin "19") (pinfunction "SWCLK/PIO0_10/SCK0/CT16B0_MAT2_19") (pintype "bidirectional"))
    )
    (net (code "19") (name "IF_SWDIO") (class "Default")
      (node (ref "CON2") (pin "2") (pinfunction "SWDIO/TMS_2") (pintype "passive"))
      (node (ref "U3") (pin "25") (pinfunction "SWDIO/PIO0_15/AD4/CT32B1_MAT2_25") (pintype "bidirectional"))
    )
    (net (code "20") (name "LED_COM_GREEN") (class "Default")
      (node (ref "LED2") (pin "C") (pinfunction "C_C") (pintype "passive"))
      (node (ref "U3") (pin "21") (pinfunction "TDI/PIO0_11/AD0/CT32B0_MAT3_21") (pintype "bidirectional"))
    )
    (net (code "21") (name "LED_DAP_BLUE") (class "Default")
      (node (ref "LED1") (pin "C") (pinfunction "C_C") (pintype "passive"))
      (node (ref "U3") (pin "12") (pinfunction "PIO0_21/CT16B1_MAT0/MOSI1_12") (pintype "bidirectional"))
    )
    (net (code "22") (name "LED_PWR_RED") (class "Default")
      (node (ref "LED3") (pin "C") (pinfunction "C_C") (pintype "passive"))
      (node (ref "U3") (pin "7") (pinfunction "PIO0_20/CT16B1_CAP0_7") (pintype "bidirectional"))
    )
    (net (code "23") (name "Net-(C6-P$1)") (class "Default")
      (node (ref "C6") (pin "1") (pinfunction "P$1_1") (pintype "passive"))
      (node (ref "Q1") (pin "P$1") (pinfunction "1_P$1") (pintype "passive"))
      (node (ref "U3") (pin "5") (pinfunction "XTALOUT_5") (pintype "output"))
    )
    (net (code "24") (name "Net-(C7-P$1)") (class "Default")
      (node (ref "C7") (pin "1") (pinfunction "P$1_1") (pintype "passive"))
      (node (ref "Q1") (pin "P$3") (pinfunction "2_P$3") (pintype "passive"))
      (node (ref "U3") (pin "4") (pinfunction "XTALIN_4") (pintype "input"))
    )
    (net (code "25") (name "Net-(C8-P$1)") (class "Default")
      (node (ref "C8") (pin "1") (pinfunction "P$1_1") (pintype "passive"))
      (node (ref "R8") (pin "2") (pinfunction "P$2_2") (pintype "passive"))
      (node (ref "U3") (pin "13") (pinfunction "USB_DM_13") (pintype "bidirectional"))
    )
    (net (code "26") (name "Net-(C9-P$1)") (class "Default")
      (node (ref "C9") (pin "1") (pinfunction "P$1_1") (pintype "passive"))
      (node (ref "R7") (pin "2") (pinfunction "P$2_2") (pintype "passive"))
      (node (ref "R9") (pin "2") (pinfunction "P$2_2") (pintype "passive"))
      (node (ref "U3") (pin "14") (pinfunction "USB_DP_14") (pintype "bidirectional"))
    )
    (net (code "27") (name "Net-(C19-P$1)") (class "Default")
      (node (ref "C19") (pin "1") (pinfunction "P$1_1") (pintype "passive"))
      (node (ref "MOD2") (pin "25") (pinfunction "SIO_00/XL1_25") (pintype "bidirectional"))
      (node (ref "Q2") (pin "X1") (pinfunction "1_X1") (pintype "passive"))
    )
    (net (code "28") (name "Net-(C20-P$1)") (class "Default")
      (node (ref "C20") (pin "1") (pinfunction "P$1_1") (pintype "passive"))
      (node (ref "MOD2") (pin "24") (pinfunction "SIO_01/XL2_24") (pintype "bidirectional"))
      (node (ref "Q2") (pin "X2") (pinfunction "2_X2") (pintype "passive"))
    )
    (net (code "29") (name "Net-(C23-P$1)") (class "Default")
      (node (ref "C23") (pin "1") (pinfunction "P$1_1") (pintype "passive"))
      (node (ref "R18") (pin "1") (pinfunction "P$1_1") (pintype "passive"))
      (node (ref "U6") (pin "1") (pinfunction "VIN+_1") (pintype "input"))
    )
    (net (code "30") (name "Net-(C23-P$2)") (class "Default")
      (node (ref "C23") (pin "2") (pinfunction "P$2_2") (pintype "passive"))
      (node (ref "R17") (pin "1") (pinfunction "P$1_1") (pintype "passive"))
      (node (ref "U6") (pin "2") (pinfunction "VIN-_2") (pintype "input"))
    )
    (net (code "31") (name "Net-(CON1-PadD+)") (class "Default")
      (node (ref "CON1") (pin "D+") (pinfunction "D+_D+") (pintype "bidirectional"))
      (node (ref "U1") (pin "1") (pinfunction "IO1_1") (pintype "bidirectional"))
    )
    (net (code "32") (name "Net-(CON1-PadD-)") (class "Default")
      (node (ref "CON1") (pin "D-") (pinfunction "D-_D-") (pintype "bidirectional"))
      (node (ref "U1") (pin "3") (pinfunction "IO2_3") (pintype "bidirectional"))
    )
    (net (code "33") (name "Net-(IC2A-O)") (class "Default")
      (node (ref "IC2") (pin "4") (pinfunction "O_4") (pintype "tri_state"))
      (node (ref "R21") (pin "1") (pinfunction "P$1_1") (pintype "passive"))
    )
    (net (code "34") (name "Net-(IC3A-O)") (class "Default")
      (node (ref "IC3") (pin "4") (pinfunction "O_4") (pintype "tri_state"))
      (node (ref "R22") (pin "1") (pinfunction "P$1_1") (pintype "passive"))
    )
    (net (code "35") (name "Net-(IC4A-O)") (class "Default")
      (node (ref "IC4") (pin "4") (pinfunction "O_4") (pintype "tri_state"))
      (node (ref "R23") (pin "1") (pinfunction "P$1_1") (pintype "passive"))
    )
    (net (code "36") (name "Net-(MOD2-SIO_09{slash}NFC1)") (class "Default")
      (node (ref "CON4") (pin "RF") (pinfunction "RF_RF") (pintype "bidirectional"))
      (node (ref "MOD2") (pin "15") (pinfunction "SIO_09/NFC1_15") (pintype "bidirectional"))
    )
    (net (code "37") (name "Net-(MOD2-SIO_10{slash}NFC2)") (class "Default")
      (node (ref "CON4") (pin "GND1") (pinfunction "GND_GND1") (pintype "bidirectional"))
      (node (ref "CON4") (pin "GND2") (pinfunction "GND_GND2") (pintype "bidirectional"))
      (node (ref "MOD2") (pin "14") (pinfunction "SIO_10/NFC2_14") (pintype "bidirectional"))
    )
    (net (code "38") (name "Net-(MOD2-SIO_25{slash}SPI_SCK)") (class "Default")
      (node (ref "LED7") (pin "C") (pinfunction "C_C") (pintype "passive"))
      (node (ref "MOD2") (pin "38") (pinfunction "SIO_25/SPI_SCK_38") (pintype "bidirectional"))
    )
    (net (code "39") (name "Net-(R2-P$2)") (class "Default")
      (node (ref "R2") (pin "2") (pinfunction "P$2_2") (pintype "passive"))
      (node (ref "U3") (pin "9") (pinfunction "PIO0_3/USB_VBUS_9") (pintype "bidirectional"))
    )
    (net (code "40") (name "Net-(R5-P$2)") (class "Default")
      (node (ref "D1") (pin "K") (pinfunction "K_K") (pintype "passive"))
      (node (ref "R5") (pin "2") (pinfunction "P$2_2") (pintype "passive"))
      (node (ref "R6") (pin "2") (pinfunction "P$2_2") (pintype "passive"))
      (node (ref "SW1") (pin "P$2") (pinfunction "S_P$2") (pintype "passive"))
    )
    (net (code "41") (name "Net-(R7-P$1)") (class "Default")
      (node (ref "R7") (pin "1") (pinfunction "P$1_1") (pintype "passive"))
      (node (ref "T1") (pin "3") (pinfunction "D_3") (pintype "passive"))
    )
    (net (code "42") (name "Net-(R10-P$1)") (class "Default")
      (node (ref "LED1") (pin "A") (pinfunction "A_A") (pintype "passive"))
      (node (ref "R10") (pin "1") (pinfunction "P$1_1") (pintype "passive"))
    )
    (net (code "43") (name "Net-(R11-P$1)") (class "Default")
      (node (ref "LED2") (pin "A") (pinfunction "A_A") (pintype "passive"))
      (node (ref "R11") (pin "1") (pinfunction "P$1_1") (pintype "passive"))
    )
    (net (code "44") (name "Net-(R12-P$1)") (class "Default")
      (node (ref "LED3") (pin "A") (pinfunction "A_A") (pintype "passive"))
      (node (ref "R12") (pin "1") (pinfunction "P$1_1") (pintype "passive"))
    )
    (net (code "45") (name "Net-(R21-P$2)") (class "Default")
      (node (ref "LED4") (pin "A") (pinfunction "A_A") (pintype "passive"))
      (node (ref "R21") (pin "2") (pinfunction "P$2_2") (pintype "passive"))
    )
    (net (code "46") (name "Net-(R22-P$2)") (class "Default")
      (node (ref "LED5") (pin "A") (pinfunction "A_A") (pintype "passive"))
      (node (ref "R22") (pin "2") (pinfunction "P$2_2") (pintype "passive"))
    )
    (net (code "47") (name "Net-(R23-P$2)") (class "Default")
      (node (ref "LED6") (pin "A") (pinfunction "A_A") (pintype "passive"))
      (node (ref "R23") (pin "2") (pinfunction "P$2_2") (pintype "passive"))
    )
    (net (code "48") (name "Net-(R24-P$2)") (class "Default")
      (node (ref "R24") (pin "2") (pinfunction "P$2_2") (pintype "passive"))
      (node (ref "SW2") (pin "P$2") (pinfunction "S_P$2") (pintype "passive"))
    )
    (net (code "49") (name "Net-(R25-P$2)") (class "Default")
      (node (ref "R25") (pin "2") (pinfunction "P$2_2") (pintype "passive"))
      (node (ref "SW3") (pin "P$2") (pinfunction "S_P$2") (pintype "passive"))
    )
    (net (code "50") (name "Net-(R26-P$1)") (class "Default")
      (node (ref "LED7") (pin "A") (pinfunction "A_A") (pintype "passive"))
      (node (ref "R26") (pin "1") (pinfunction "P$1_1") (pintype "passive"))
    )
    (net (code "51") (name "PA4") (class "Default")
      (node (ref "IC2") (pin "2") (pinfunction "I_2") (pintype "input"))
      (node (ref "MOD1") (pin "38") (pinfunction "PA4/ADC1.4_38") (pintype "bidirectional"))
    )
    (net (code "52") (name "PA5") (class "Default")
      (node (ref "IC3") (pin "2") (pinfunction "I_2") (pintype "input"))
      (node (ref "MOD1") (pin "34") (pinfunction "PA5/ADC1.5_34") (pintype "bidirectional"))
    )
    (net (code "53") (name "PB0") (class "Default")
      (node (ref "IC4") (pin "2") (pinfunction "I_2") (pintype "input"))
      (node (ref "MOD1") (pin "37") (pinfunction "PB0/ADC1.8_37") (pintype "bidirectional"))
    )
    (net (code "54") (name "PB4") (class "Default")
      (node (ref "MOD1") (pin "31") (pinfunction "PB4_31") (pintype "bidirectional"))
      (node (ref "SW3") (pin "P$1") (pinfunction "P_P$1") (pintype "passive"))
    )
    (net (code "55") (name "PB10") (class "Default")
      (node (ref "MOD1") (pin "19") (pinfunction "PB10_19") (pintype "bidirectional"))
      (node (ref "SW2") (pin "P$1") (pinfunction "P_P$1") (pintype "passive"))
    )
    (net (code "56") (name "PIO0_12") (class "Default")
      (node (ref "U3") (pin "22") (pinfunction "TMS/PIO0_12/AD1/CT32B1_CAP0_22") (pintype "bidirectional"))
    )
    (net (code "57") (name "PIO0_14") (class "Default")
      (node (ref "U3") (pin "24") (pinfunction "~{TRST}/PIO0_14/AD3/CT32B1_MAT1_24") (pintype "bidirectional"))
    )
    (net (code "58") (name "PIO0_15") (class "Default")
      (node (ref "U3") (pin "28") (pinfunction "PIO1_15/~{DCD}/CT16B0_MAT2/SCK1_28") (pintype "bidirectional"))
    )
    (net (code "59") (name "PIO0_16") (class "Default")
      (node (ref "U3") (pin "26") (pinfunction "PIO0_16/AD5/CT32B1_MAT3/WAKEUP_26") (pintype "bidirectional"))
    )
    (net (code "60") (name "PIO0_22") (class "Default")
      (node (ref "U3") (pin "20") (pinfunction "PIO0_22/AD6/CT16B1_MAT1/MISO1_20") (pintype "bidirectional"))
    )
    (net (code "61") (name "PIO0_23") (class "Default")
      (node (ref "U3") (pin "27") (pinfunction "PIO0_23/AD7_27") (pintype "bidirectional"))
    )
    (net (code "62") (name "PIO_13") (class "Default")
      (node (ref "U3") (pin "23") (pinfunction "TDO/PIO0_13/AD2/CT32B1_MAT0_23") (pintype "bidirectional"))
    )
    (net (code "63") (name "SFLASH_CS") (class "Default")
      (node (ref "MOD2") (pin "12") (pinfunction "SIO_12/SFLASH_CS_12") (pintype "bidirectional"))
      (node (ref "U5") (pin "1") (pinfunction "~{CS}_1") (pintype "bidirectional"))
    )
    (net (code "64") (name "SFLASH_MISO") (class "Default")
      (node (ref "MOD2") (pin "11") (pinfunction "SIO_14/SFLASH_MISO_11") (pintype "bidirectional"))
      (node (ref "U5") (pin "2") (pinfunction "SO_2") (pintype "bidirectional"))
    )
    (net (code "65") (name "SFLASH_MOSI") (class "Default")
      (node (ref "MOD2") (pin "8") (pinfunction "SIO_20/SFLASH_MOSI_8") (pintype "bidirectional"))
      (node (ref "U5") (pin "5") (pinfunction "SI_5") (pintype "bidirectional"))
    )
    (net (code "66") (name "SFLASH_SCK") (class "Default")
      (node (ref "MOD2") (pin "10") (pinfunction "SIO_16/SFLASH_SCK_10") (pintype "bidirectional"))
      (node (ref "U5") (pin "6") (pinfunction "SCK_6") (pintype "bidirectional"))
    )
    (net (code "67") (name "TGT_CTS") (class "Default")
      (node (ref "U3") (pin "30") (pinfunction "PIO0_17/~{RTS}/CT32B0_CAP0/SCLK_30") (pintype "bidirectional"))
    )
    (net (code "68") (name "TGT_NRESET") (class "Default")
      (node (ref "D1") (pin "A") (pinfunction "A_A") (pintype "passive"))
      (node (ref "J1") (pin "2") (pinfunction "2_2") (pintype "passive"))
      (node (ref "U3") (pin "8") (pinfunction "PIO0_2/SSEL0/CT16B0_CAP0_8") (pintype "bidirectional"))
    )
    (net (code "69") (name "TGT_NRESET_BL652") (class "Default")
      (node (ref "C16") (pin "1") (pinfunction "P$1_1") (pintype "passive"))
      (node (ref "CON3") (pin "3") (pinfunction "NRESET_3") (pintype "passive"))
      (node (ref "J1") (pin "3") (pinfunction "3_3") (pintype "passive"))
      (node (ref "MOD2") (pin "7") (pinfunction "~{RESET}_7") (pintype "bidirectional"))
      (node (ref "R16") (pin "1") (pinfunction "P$1_1") (pintype "passive"))
    )
    (net (code "70") (name "TGT_NRESET_EMW3166") (class "Default")
      (node (ref "C11") (pin "1") (pinfunction "P$1_1") (pintype "passive"))
      (node (ref "J1") (pin "1") (pinfunction "1_1") (pintype "passive"))
      (node (ref "MOD1") (pin "13") (pinfunction "~{RESET}_13") (pintype "bidirectional"))
      (node (ref "R13") (pin "1") (pinfunction "P$1_1") (pintype "passive"))
    )
    (net (code "71") (name "TGT_NRESET_FB") (class "Default")
      (node (ref "R5") (pin "1") (pinfunction "P$1_1") (pintype "passive"))
      (node (ref "U3") (pin "3") (pinfunction "PIO0_1/CLKOUT/CT32B0_MAT2/USB_FTOGGLE_3") (pintype "bidirectional"))
    )
    (net (code "72") (name "TGT_NRESET_FB_ISP") (class "Default")
      (node (ref "R6") (pin "1") (pinfunction "P$1_1") (pintype "passive"))
      (node (ref "U3") (pin "1") (pinfunction "PIO1_19/~{DTR}/SSEL1_1") (pintype "bidirectional"))
    )
    (net (code "73") (name "TGT_RTS") (class "Default")
      (node (ref "R4") (pin "2") (pinfunction "P$2_2") (pintype "passive"))
      (node (ref "U3") (pin "16") (pinfunction "PIO0_7/~{CTS}_16") (pintype "bidirectional"))
    )
    (net (code "74") (name "TGT_RX") (class "Default")
      (node (ref "MOD1") (pin "12") (pinfunction "PC7/RX6_12") (pintype "bidirectional"))
      (node (ref "U3") (pin "32") (pinfunction "PIO0_19/TXD/CT32B0_MAT1_32") (pintype "bidirectional"))
    )
    (net (code "75") (name "TGT_SWCLK") (class "Default")
      (node (ref "J3") (pin "2") (pinfunction "2_2") (pintype "passive"))
      (node (ref "R4") (pin "1") (pinfunction "P$1_1") (pintype "passive"))
      (node (ref "U3") (pin "18") (pinfunction "PIO0_9/MOSI0/CT16B0_MAT1_18") (pintype "bidirectional"))
    )
    (net (code "76") (name "TGT_SWCLK_BL652") (class "Default")
      (node (ref "CON3") (pin "4") (pinfunction "SWCLK/TCLK_4") (pintype "passive"))
      (node (ref "J3") (pin "3") (pinfunction "3_3") (pintype "passive"))
      (node (ref "MOD2") (pin "6") (pinfunction "SWDCLK_6") (pintype "bidirectional"))
    )
    (net (code "77") (name "TGT_SWCLK_EMW3166") (class "Default")
      (node (ref "J3") (pin "1") (pinfunction "1_1") (pintype "passive"))
      (node (ref "MOD1") (pin "25") (pinfunction "PA14/SWCLK_25") (pintype "bidirectional"))
    )
    (net (code "78") (name "TGT_SWDIO") (class "Default")
      (node (ref "J2") (pin "2") (pinfunction "2_2") (pintype "passive"))
      (node (ref "U3") (pin "17") (pinfunction "PIO0_8/MISO0/CT16B0_MAT0_17") (pintype "bidirectional"))
    )
    (net (code "79") (name "TGT_SWDIO_BL652") (class "Default")
      (node (ref "CON3") (pin "2") (pinfunction "SWDIO/TMS_2") (pintype "passive"))
      (node (ref "J2") (pin "3") (pinfunction "3_3") (pintype "passive"))
      (node (ref "MOD1") (pin "33") (pinfunction "PA10_33") (pintype "bidirectional"))
      (node (ref "MOD2") (pin "5") (pinfunction "SWDIO_5") (pintype "bidirectional"))
    )
    (net (code "80") (name "TGT_SWDIO_EMW3166") (class "Default")
      (node (ref "J2") (pin "1") (pinfunction "1_1") (pintype "passive"))
      (node (ref "MOD1") (pin "26") (pinfunction "PA13/SWDIO_26") (pintype "bidirectional"))
    )
    (net (code "81") (name "TGT_TX") (class "Default")
      (node (ref "MOD1") (pin "8") (pinfunction "PC6/TX6_8") (pintype "bidirectional"))
      (node (ref "U3") (pin "31") (pinfunction "PIO0_18/RXD/CT32B0_MAT0_31") (pintype "bidirectional"))
    )
    (net (code "82") (name "USB-D+") (class "Default")
      (node (ref "R9") (pin "1") (pinfunction "P$1_1") (pintype "passive"))
      (node (ref "U1") (pin "6") (pinfunction "IO1_6") (pintype "bidirectional"))
    )
    (net (code "83") (name "USB-D-") (class "Default")
      (node (ref "R8") (pin "1") (pinfunction "P$1_1") (pintype "passive"))
      (node (ref "U1") (pin "4") (pinfunction "IO2_4") (pintype "bidirectional"))
    )
    (net (code "84") (name "USB-SCON") (class "Default")
      (node (ref "T1") (pin "1") (pinfunction "G_1") (pintype "passive"))
      (node (ref "U3") (pin "15") (pinfunction "PIO0_6/~{USB_CONNECT}/SCK0_15") (pintype "bidirectional"))
    )
    (net (code "85") (name "unconnected-(CON2-SWO{slash}TDO-Pad6)") (class "Default")
      (node (ref "CON2") (pin "6") (pinfunction "SWO/TDO_6") (pintype "passive"))
    )
    (net (code "86") (name "unconnected-(CON3-SWO{slash}TDO-Pad6)") (class "Default")
      (node (ref "CON3") (pin "6") (pinfunction "SWO/TDO_6") (pintype "passive"))
    )
    (net (code "87") (name "unconnected-(IC1-NC1-Pad1)") (class "Default")
      (node (ref "IC1") (pin "1") (pinfunction "NC1_1") (pintype "bidirectional"))
    )
    (net (code "88") (name "unconnected-(IC1-NC2-Pad2)") (class "Default")
      (node (ref "IC1") (pin "2") (pinfunction "NC2_2") (pintype "bidirectional"))
    )
    (net (code "89") (name "unconnected-(IC1-NC3-Pad3)") (class "Default")
      (node (ref "IC1") (pin "3") (pinfunction "NC3_3") (pintype "bidirectional"))
    )
    (net (code "90") (name "unconnected-(IC1-NC7-Pad7)") (class "Default")
      (node (ref "IC1") (pin "7") (pinfunction "NC7_7") (pintype "bidirectional"))
    )
    (net (code "91") (name "unconnected-(MOD1-ANT-Pad41)") (class "Default")
      (node (ref "MOD1") (pin "41") (pinfunction "ANT_41") (pintype "bidirectional"))
    )
    (net (code "92") (name "unconnected-(MOD1-PB2-Pad2)") (class "Default")
      (node (ref "MOD1") (pin "2") (pinfunction "PB2_2") (pintype "bidirectional"))
    )
    (net (code "93") (name "unconnected-(MOD1-PB3-Pad27)") (class "Default")
      (node (ref "MOD1") (pin "27") (pinfunction "PB3_27") (pintype "bidirectional"))
    )
    (net (code "94") (name "unconnected-(MOD1-PB12{slash}NSS2-Pad5)") (class "Default")
      (node (ref "MOD1") (pin "5") (pinfunction "PB12/NSS2_5") (pintype "bidirectional"))
    )
    (net (code "95") (name "unconnected-(MOD1-PC0-Pad14)") (class "Default")
      (node (ref "MOD1") (pin "14") (pinfunction "PC0_14") (pintype "bidirectional"))
    )
    (net (code "96") (name "unconnected-(MOD1-PC13-Pad16)") (class "Default")
      (node (ref "MOD1") (pin "16") (pinfunction "PC13_16") (pintype "bidirectional"))
    )
    (net (code "97") (name "unconnected-(MOD2-SIO_02{slash}AIN0-Pad23)") (class "Default")
      (node (ref "MOD2") (pin "23") (pinfunction "SIO_02/AIN0_23") (pintype "bidirectional"))
    )
    (net (code "98") (name "unconnected-(MOD2-SIO_03{slash}AIN1-Pad22)") (class "Default")
      (node (ref "MOD2") (pin "22") (pinfunction "SIO_03/AIN1_22") (pintype "bidirectional"))
    )
    (net (code "99") (name "unconnected-(MOD2-SIO_04{slash}AIN2-Pad21)") (class "Default")
      (node (ref "MOD2") (pin "21") (pinfunction "SIO_04/AIN2_21") (pintype "bidirectional"))
    )
    (net (code "100") (name "unconnected-(MOD2-SIO_11-Pad13)") (class "Default")
      (node (ref "MOD2") (pin "13") (pinfunction "SIO_11_13") (pintype "bidirectional"))
    )
    (net (code "101") (name "unconnected-(MOD2-SIO_13{slash}~{AUTORUN}-Pad28)") (class "Default")
      (node (ref "MOD2") (pin "28") (pinfunction "SIO_13/~{AUTORUN}_28") (pintype "bidirectional"))
    )
    (net (code "102") (name "unconnected-(MOD2-SIO_15-Pad29)") (class "Default")
      (node (ref "MOD2") (pin "29") (pinfunction "SIO_15_29") (pintype "bidirectional"))
    )
    (net (code "103") (name "unconnected-(MOD2-SIO_17-Pad30)") (class "Default")
      (node (ref "MOD2") (pin "30") (pinfunction "SIO_17_30") (pintype "bidirectional"))
    )
    (net (code "104") (name "unconnected-(MOD2-SIO_18-Pad9)") (class "Default")
      (node (ref "MOD2") (pin "9") (pinfunction "SIO_18_9") (pintype "bidirectional"))
    )
    (net (code "105") (name "unconnected-(MOD2-SIO_19-Pad31)") (class "Default")
      (node (ref "MOD2") (pin "31") (pinfunction "SIO_19_31") (pintype "bidirectional"))
    )
    (net (code "106") (name "unconnected-(MOD2-SIO_22-Pad4)") (class "Default")
      (node (ref "MOD2") (pin "4") (pinfunction "SIO_22_4") (pintype "bidirectional"))
    )
    (net (code "107") (name "unconnected-(MOD2-SIO_23{slash}SPI_MOSI-Pad3)") (class "Default")
      (node (ref "MOD2") (pin "3") (pinfunction "SIO_23/SPI_MOSI_3") (pintype "bidirectional"))
    )
    (net (code "108") (name "unconnected-(MOD2-SIO_24{slash}SPI_MISO-Pad2)") (class "Default")
      (node (ref "MOD2") (pin "2") (pinfunction "SIO_24/SPI_MISO_2") (pintype "bidirectional"))
    )
    (net (code "109") (name "unconnected-(MOD2-SIO_28{slash}AIN4-Pad35)") (class "Default")
      (node (ref "MOD2") (pin "35") (pinfunction "SIO_28/AIN4_35") (pintype "bidirectional"))
    )
    (net (code "110") (name "unconnected-(MOD2-SIO_29{slash}AIN5-Pad34)") (class "Default")
      (node (ref "MOD2") (pin "34") (pinfunction "SIO_29/AIN5_34") (pintype "bidirectional"))
    )
    (net (code "111") (name "unconnected-(MOD2-SIO_30{slash}AIN6-Pad33)") (class "Default")
      (node (ref "MOD2") (pin "33") (pinfunction "SIO_30/AIN6_33") (pintype "bidirectional"))
    )
    (net (code "112") (name "unconnected-(MOD2-SIO_31{slash}AIN7-Pad32)") (class "Default")
      (node (ref "MOD2") (pin "32") (pinfunction "SIO_31/AIN7_32") (pintype "bidirectional"))
    )
  )
)
